# Schematic.net
KiCad netlist of a schematic drawn in Altium Designer
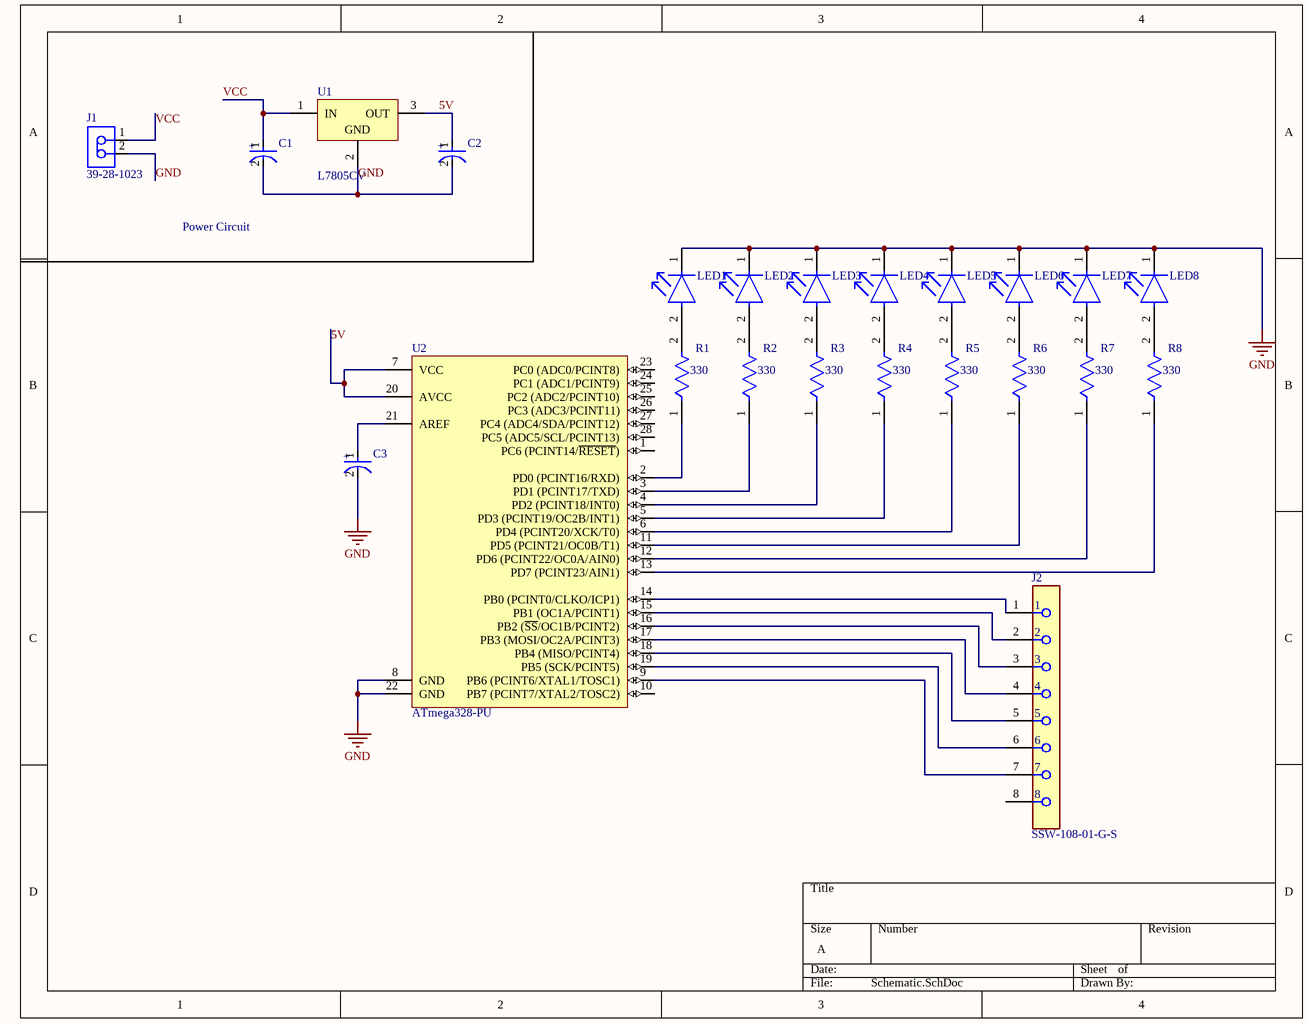
[diagram p0: Schematic.SchDoc]

(export (version "E")
  (design (tool "Eeschema 10.0.6"))
  (components
    (comp (ref "C1")
      (value "300nF")
      (footprint "FP-EEU-FC1V221L-MFG")
      (description "CAP ALUM 220UF 20% 35V RADIAL")
      (fields
        (field (name "OCTOPART") "https://octopart.com/eeu-fc1v221l-panasonic-39478519")
        (field (name "MANUFACTURER") "Panasonic Electronic Components")
      )
      (libsource (lib "Altium Content Vault") (part "385ce6c70a3ab0aa1e866f00bd8ed49"))
    )
    (comp (ref "C2")
      (value "100nF")
      (footprint "FP-EEU-FC1V221L-MFG")
      (description "CAP ALUM 220UF 20% 35V RADIAL")
      (fields
        (field (name "OCTOPART") "https://octopart.com/eeu-fc1v221l-panasonic-39478519")
        (field (name "MANUFACTURER") "Panasonic Electronic Components")
      )
      (libsource (lib "Altium Content Vault") (part "385ce6c70a3ab0aa1e866f00bd8ed49"))
    )
    (comp (ref "C3")
      (value "100nF")
      (footprint "FP-EEU-FC1V221L-MFG")
      (description "CAP ALUM 220UF 20% 35V RADIAL")
      (fields
        (field (name "OCTOPART") "https://octopart.com/eeu-fc1v221l-panasonic-39478519")
        (field (name "MANUFACTURER") "Panasonic Electronic Components")
      )
      (libsource (lib "Altium Content Vault") (part "385ce6c70a3ab0aa1e866f00bd8ed49"))
    )
    (comp (ref "J1")
      (value "39-28-1023")
      (footprint "MOLX-39-28-1023-2_V")
      (fields (field (name "MANUFACTURER") "Molex"))
      (libsource (lib "Altium Content Vault") (part "CN-2P-F-QF2"))
    )
    (comp (ref "J2")
      (value "SSW-108-01-G-S")
      (footprint "FP-SSW-108-01-G-S-MFG")
      (description "CONN RCPT 8POS 0.1 GOLD PCB")
      (libsource (lib "Altium Content Vault") (part "a32a9c29f5c2290c50060dfb8ad7212"))
    )
    (comp (ref "LED1")
      (value "HLMP-1719")
      (footprint "FP-HLMP-1719-MFG")
      (description "LED YELLOW DIFFUSED T-1 T/H")
      (fields
        (field (name "MANUFACTURER") "Broadcom")
        (field (name "OCTOPART") "https://octopart.com/hlmp-1719-broadcom-71130405")
      )
      (libsource (lib "Altium Content Vault") (part "8706943c75ba83719d021d2fdc84c58"))
    )
    (comp (ref "LED2")
      (value "HLMP-1719")
      (footprint "FP-HLMP-1719-MFG")
      (description "LED YELLOW DIFFUSED T-1 T/H")
      (fields
        (field (name "MANUFACTURER") "Broadcom")
        (field (name "OCTOPART") "https://octopart.com/hlmp-1719-broadcom-71130405")
      )
      (libsource (lib "Altium Content Vault") (part "8706943c75ba83719d021d2fdc84c58"))
    )
    (comp (ref "LED3")
      (value "HLMP-1719")
      (footprint "FP-HLMP-1719-MFG")
      (description "LED YELLOW DIFFUSED T-1 T/H")
      (fields
        (field (name "MANUFACTURER") "Broadcom")
        (field (name "OCTOPART") "https://octopart.com/hlmp-1719-broadcom-71130405")
      )
      (libsource (lib "Altium Content Vault") (part "8706943c75ba83719d021d2fdc84c58"))
    )
    (comp (ref "LED4")
      (value "HLMP-1719")
      (footprint "FP-HLMP-1719-MFG")
      (description "LED YELLOW DIFFUSED T-1 T/H")
      (fields
        (field (name "MANUFACTURER") "Broadcom")
        (field (name "OCTOPART") "https://octopart.com/hlmp-1719-broadcom-71130405")
      )
      (libsource (lib "Altium Content Vault") (part "8706943c75ba83719d021d2fdc84c58"))
    )
    (comp (ref "LED5")
      (value "HLMP-1719")
      (footprint "FP-HLMP-1719-MFG")
      (description "LED YELLOW DIFFUSED T-1 T/H")
      (fields
        (field (name "MANUFACTURER") "Broadcom")
        (field (name "OCTOPART") "https://octopart.com/hlmp-1719-broadcom-71130405")
      )
      (libsource (lib "Altium Content Vault") (part "8706943c75ba83719d021d2fdc84c58"))
    )
    (comp (ref "LED6")
      (value "HLMP-1719")
      (footprint "FP-HLMP-1719-MFG")
      (description "LED YELLOW DIFFUSED T-1 T/H")
      (fields
        (field (name "MANUFACTURER") "Broadcom")
        (field (name "OCTOPART") "https://octopart.com/hlmp-1719-broadcom-71130405")
      )
      (libsource (lib "Altium Content Vault") (part "8706943c75ba83719d021d2fdc84c58"))
    )
    (comp (ref "LED7")
      (value "HLMP-1719")
      (footprint "FP-HLMP-1719-MFG")
      (description "LED YELLOW DIFFUSED T-1 T/H")
      (fields
        (field (name "MANUFACTURER") "Broadcom")
        (field (name "OCTOPART") "https://octopart.com/hlmp-1719-broadcom-71130405")
      )
      (libsource (lib "Altium Content Vault") (part "8706943c75ba83719d021d2fdc84c58"))
    )
    (comp (ref "LED8")
      (value "HLMP-1719")
      (footprint "FP-HLMP-1719-MFG")
      (description "LED YELLOW DIFFUSED T-1 T/H")
      (fields
        (field (name "MANUFACTURER") "Broadcom")
        (field (name "OCTOPART") "https://octopart.com/hlmp-1719-broadcom-71130405")
      )
      (libsource (lib "Altium Content Vault") (part "8706943c75ba83719d021d2fdc84c58"))
    )
    (comp (ref "R1")
      (value "330")
      (footprint "FP-MFR-25-MFG")
      (description "RES 1.18K OHM 1/4W 1% AXIAL")
      (fields (field (name "MANUFACTURER") "Yageo") (field (name "TOLERANCE") "1%"))
      (libsource (lib "Altium Content Vault") (part "1029c3af85768c4190bb7ad29bc67b5"))
    )
    (comp (ref "R2")
      (value "330")
      (footprint "FP-MFR-25-MFG")
      (description "RES 1.18K OHM 1/4W 1% AXIAL")
      (fields (field (name "MANUFACTURER") "Yageo") (field (name "TOLERANCE") "1%"))
      (libsource (lib "Altium Content Vault") (part "1029c3af85768c4190bb7ad29bc67b5"))
    )
    (comp (ref "R3")
      (value "330")
      (footprint "FP-MFR-25-MFG")
      (description "RES 1.18K OHM 1/4W 1% AXIAL")
      (fields (field (name "MANUFACTURER") "Yageo") (field (name "TOLERANCE") "1%"))
      (libsource (lib "Altium Content Vault") (part "1029c3af85768c4190bb7ad29bc67b5"))
    )
    (comp (ref "R4")
      (value "330")
      (footprint "FP-MFR-25-MFG")
      (description "RES 1.18K OHM 1/4W 1% AXIAL")
      (fields (field (name "MANUFACTURER") "Yageo") (field (name "TOLERANCE") "1%"))
      (libsource (lib "Altium Content Vault") (part "1029c3af85768c4190bb7ad29bc67b5"))
    )
    (comp (ref "R5")
      (value "330")
      (footprint "FP-MFR-25-MFG")
      (description "RES 1.18K OHM 1/4W 1% AXIAL")
      (fields (field (name "MANUFACTURER") "Yageo") (field (name "TOLERANCE") "1%"))
      (libsource (lib "Altium Content Vault") (part "1029c3af85768c4190bb7ad29bc67b5"))
    )
    (comp (ref "R6")
      (value "330")
      (footprint "FP-MFR-25-MFG")
      (description "RES 1.18K OHM 1/4W 1% AXIAL")
      (fields (field (name "MANUFACTURER") "Yageo") (field (name "TOLERANCE") "1%"))
      (libsource (lib "Altium Content Vault") (part "1029c3af85768c4190bb7ad29bc67b5"))
    )
    (comp (ref "R7")
      (value "330")
      (footprint "FP-MFR-25-MFG")
      (description "RES 1.18K OHM 1/4W 1% AXIAL")
      (fields (field (name "MANUFACTURER") "Yageo") (field (name "TOLERANCE") "1%"))
      (libsource (lib "Altium Content Vault") (part "1029c3af85768c4190bb7ad29bc67b5"))
    )
    (comp (ref "R8")
      (value "330")
      (footprint "FP-MFR-25-MFG")
      (description "RES 1.18K OHM 1/4W 1% AXIAL")
      (fields (field (name "MANUFACTURER") "Yageo") (field (name "TOLERANCE") "1%"))
      (libsource (lib "Altium Content Vault") (part "1029c3af85768c4190bb7ad29bc67b5"))
    )
    (comp (ref "U1")
      (value "L7805CV")
      (footprint "TO220")
      (description "Positive Voltage Regulator, 5V, 3-Pin TO-220")
      (libsource (lib "Altium Content Vault") (part "PM-REG-L4940-SIL3"))
    )
    (comp (ref "U2")
      (value "ATmega328-PU")
      (footprint "28P3")
      (libsource (lib "Altium Content Vault") (part "MC-8B-ATM48-IL28"))
    )
  )
  (nets
    (net (code "1") (name "/5V") (class "Default")
      (node (ref "C2") (pin "1") (pinfunction "C_1") (pintype "passive"))
      (node (ref "U1") (pin "3") (pinfunction "OUT_3") (pintype "power_in"))
      (node (ref "U2") (pin "20") (pinfunction "AVCC_20") (pintype "power_in"))
      (node (ref "U2") (pin "7") (pinfunction "VCC_7") (pintype "power_in"))
    )
    (net (code "2") (name "/VCC") (class "Default")
      (node (ref "C1") (pin "1") (pinfunction "C_1") (pintype "passive"))
      (node (ref "J1") (pin "1") (pinfunction "1_1") (pintype "passive"))
      (node (ref "U1") (pin "1") (pinfunction "IN_1") (pintype "power_in"))
    )
    (net (code "3") (name "GND") (class "Default")
      (node (ref "C1") (pin "2") (pinfunction "A_2") (pintype "passive"))
      (node (ref "C2") (pin "2") (pinfunction "A_2") (pintype "passive"))
      (node (ref "C3") (pin "2") (pinfunction "A_2") (pintype "passive"))
      (node (ref "J1") (pin "2") (pinfunction "2_2") (pintype "passive"))
      (node (ref "LED1") (pin "1") (pinfunction "C_1") (pintype "passive"))
      (node (ref "LED2") (pin "1") (pinfunction "C_1") (pintype "passive"))
      (node (ref "LED3") (pin "1") (pinfunction "C_1") (pintype "passive"))
      (node (ref "LED4") (pin "1") (pinfunction "C_1") (pintype "passive"))
      (node (ref "LED5") (pin "1") (pinfunction "C_1") (pintype "passive"))
      (node (ref "LED6") (pin "1") (pinfunction "C_1") (pintype "passive"))
      (node (ref "LED7") (pin "1") (pinfunction "C_1") (pintype "passive"))
      (node (ref "LED8") (pin "1") (pinfunction "C_1") (pintype "passive"))
      (node (ref "U1") (pin "2") (pinfunction "GND_2") (pintype "power_in"))
      (node (ref "U2") (pin "22") (pinfunction "GND_22") (pintype "power_in"))
      (node (ref "U2") (pin "8") (pinfunction "GND_8") (pintype "power_in"))
    )
    (net (code "4") (name "Net-(C3-C)") (class "Default")
      (node (ref "C3") (pin "1") (pinfunction "C_1") (pintype "passive"))
      (node (ref "U2") (pin "21") (pinfunction "AREF_21") (pintype "power_in"))
    )
    (net (code "5") (name "Net-(LED1-A)") (class "Default")
      (node (ref "LED1") (pin "2") (pinfunction "A_2") (pintype "passive"))
      (node (ref "R1") (pin "2") (pinfunction "2_2") (pintype "passive"))
    )
    (net (code "6") (name "Net-(LED2-A)") (class "Default")
      (node (ref "LED2") (pin "2") (pinfunction "A_2") (pintype "passive"))
      (node (ref "R2") (pin "2") (pinfunction "2_2") (pintype "passive"))
    )
    (net (code "7") (name "Net-(LED3-A)") (class "Default")
      (node (ref "LED3") (pin "2") (pinfunction "A_2") (pintype "passive"))
      (node (ref "R3") (pin "2") (pinfunction "2_2") (pintype "passive"))
    )
    (net (code "8") (name "Net-(LED4-A)") (class "Default")
      (node (ref "LED4") (pin "2") (pinfunction "A_2") (pintype "passive"))
      (node (ref "R4") (pin "2") (pinfunction "2_2") (pintype "passive"))
    )
    (net (code "9") (name "Net-(LED5-A)") (class "Default")
      (node (ref "LED5") (pin "2") (pinfunction "A_2") (pintype "passive"))
      (node (ref "R5") (pin "2") (pinfunction "2_2") (pintype "passive"))
    )
    (net (code "10") (name "Net-(LED6-A)") (class "Default")
      (node (ref "LED6") (pin "2") (pinfunction "A_2") (pintype "passive"))
      (node (ref "R6") (pin "2") (pinfunction "2_2") (pintype "passive"))
    )
    (net (code "11") (name "Net-(LED7-A)") (class "Default")
      (node (ref "LED7") (pin "2") (pinfunction "A_2") (pintype "passive"))
      (node (ref "R7") (pin "2") (pinfunction "2_2") (pintype "passive"))
    )
    (net (code "12") (name "Net-(LED8-A)") (class "Default")
      (node (ref "LED8") (pin "2") (pinfunction "A_2") (pintype "passive"))
      (node (ref "R8") (pin "2") (pinfunction "2_2") (pintype "passive"))
    )
    (net (code "13") (name "Net-(U2-PB0_(PCINT0{slash}CLKO{slash}ICP1))") (class "Default")
      (node (ref "J2") (pin "1") (pinfunction "1_1") (pintype "passive"))
      (node (ref "U2") (pin "14") (pinfunction "PB0_(PCINT0/CLKO/ICP1)_14") (pintype "bidirectional"))
    )
    (net (code "14") (name "Net-(U2-PB1_(OC1A{slash}PCINT1))") (class "Default")
      (node (ref "J2") (pin "2") (pinfunction "2_2") (pintype "passive"))
      (node (ref "U2") (pin "15") (pinfunction "PB1_(OC1A/PCINT1)_15") (pintype "bidirectional"))
    )
    (net (code "15") (name "Net-(U2-PB2_(~{SS}{slash}OC1B{slash}PCINT2))") (class "Default")
      (node (ref "J2") (pin "3") (pinfunction "3_3") (pintype "passive"))
      (node (ref "U2") (pin "16") (pinfunction "PB2_(~{SS}/OC1B/PCINT2)_16") (pintype "bidirectional"))
    )
    (net (code "16") (name "Net-(U2-PB3_(MOSI{slash}OC2A{slash}PCINT3))") (class "Default")
      (node (ref "J2") (pin "4") (pinfunction "4_4") (pintype "passive"))
      (node (ref "U2") (pin "17") (pinfunction "PB3_(MOSI/OC2A/PCINT3)_17") (pintype "bidirectional"))
    )
    (net (code "17") (name "Net-(U2-PB4_(MISO{slash}PCINT4))") (class "Default")
      (node (ref "J2") (pin "5") (pinfunction "5_5") (pintype "passive"))
      (node (ref "U2") (pin "18") (pinfunction "PB4_(MISO/PCINT4)_18") (pintype "bidirectional"))
    )
    (net (code "18") (name "Net-(U2-PB5_(SCK{slash}PCINT5))") (class "Default")
      (node (ref "J2") (pin "6") (pinfunction "6_6") (pintype "passive"))
      (node (ref "U2") (pin "19") (pinfunction "PB5_(SCK/PCINT5)_19") (pintype "bidirectional"))
    )
    (net (code "19") (name "Net-(U2-PB6_(PCINT6{slash}XTAL1{slash}TOSC1))") (class "Default")
      (node (ref "J2") (pin "7") (pinfunction "7_7") (pintype "passive"))
      (node (ref "U2") (pin "9") (pinfunction "PB6_(PCINT6/XTAL1/TOSC1)_9") (pintype "bidirectional"))
    )
    (net (code "20") (name "Net-(U2-PD0_(PCINT16{slash}RXD))") (class "Default")
      (node (ref "R1") (pin "1") (pinfunction "1_1") (pintype "passive"))
      (node (ref "U2") (pin "2") (pinfunction "PD0_(PCINT16/RXD)_2") (pintype "bidirectional"))
    )
    (net (code "21") (name "Net-(U2-PD1_(PCINT17{slash}TXD))") (class "Default")
      (node (ref "R2") (pin "1") (pinfunction "1_1") (pintype "passive"))
      (node (ref "U2") (pin "3") (pinfunction "PD1_(PCINT17/TXD)_3") (pintype "bidirectional"))
    )
    (net (code "22") (name "Net-(U2-PD2_(PCINT18{slash}INT0))") (class "Default")
      (node (ref "R3") (pin "1") (pinfunction "1_1") (pintype "passive"))
      (node (ref "U2") (pin "4") (pinfunction "PD2_(PCINT18/INT0)_4") (pintype "bidirectional"))
    )
    (net (code "23") (name "Net-(U2-PD3_(PCINT19{slash}OC2B{slash}INT1))") (class "Default")
      (node (ref "R4") (pin "1") (pinfunction "1_1") (pintype "passive"))
      (node (ref "U2") (pin "5") (pinfunction "PD3_(PCINT19/OC2B/INT1)_5") (pintype "bidirectional"))
    )
    (net (code "24") (name "Net-(U2-PD4_(PCINT20{slash}XCK{slash}T0))") (class "Default")
      (node (ref "R5") (pin "1") (pinfunction "1_1") (pintype "passive"))
      (node (ref "U2") (pin "6") (pinfunction "PD4_(PCINT20/XCK/T0)_6") (pintype "bidirectional"))
    )
    (net (code "25") (name "Net-(U2-PD5_(PCINT21{slash}OC0B{slash}T1))") (class "Default")
      (node (ref "R6") (pin "1") (pinfunction "1_1") (pintype "passive"))
      (node (ref "U2") (pin "11") (pinfunction "PD5_(PCINT21/OC0B/T1)_11") (pintype "bidirectional"))
    )
    (net (code "26") (name "Net-(U2-PD6_(PCINT22{slash}OC0A{slash}AIN0))") (class "Default")
      (node (ref "R7") (pin "1") (pinfunction "1_1") (pintype "passive"))
      (node (ref "U2") (pin "12") (pinfunction "PD6_(PCINT22/OC0A/AIN0)_12") (pintype "bidirectional"))
    )
    (net (code "27") (name "Net-(U2-PD7_(PCINT23{slash}AIN1))") (class "Default")
      (node (ref "R8") (pin "1") (pinfunction "1_1") (pintype "passive"))
      (node (ref "U2") (pin "13") (pinfunction "PD7_(PCINT23/AIN1)_13") (pintype "bidirectional"))
    )
    (net (code "28") (name "unconnected-(J2-Pad8)") (class "Default")
      (node (ref "J2") (pin "8") (pinfunction "8_8") (pintype "passive"))
    )
    (net (code "29") (name "unconnected-(U2-PB7_(PCINT7{slash}XTAL2{slash}TOSC2)-Pad10)") (class "Default")
      (node (ref "U2") (pin "10") (pinfunction "PB7_(PCINT7/XTAL2/TOSC2)_10") (pintype "bidirectional"))
    )
    (net (code "30") (name "unconnected-(U2-PC0_(ADC0{slash}PCINT8)-Pad23)") (class "Default")
      (node (ref "U2") (pin "23") (pinfunction "PC0_(ADC0/PCINT8)_23") (pintype "bidirectional"))
    )
    (net (code "31") (name "unconnected-(U2-PC1_(ADC1{slash}PCINT9)-Pad24)") (class "Default")
      (node (ref "U2") (pin "24") (pinfunction "PC1_(ADC1/PCINT9)_24") (pintype "bidirectional"))
    )
    (net (code "32") (name "unconnected-(U2-PC2_(ADC2{slash}PCINT10)-Pad25)") (class "Default")
      (node (ref "U2") (pin "25") (pinfunction "PC2_(ADC2/PCINT10)_25") (pintype "bidirectional"))
    )
    (net (code "33") (name "unconnected-(U2-PC3_(ADC3{slash}PCINT11)-Pad26)") (class "Default")
      (node (ref "U2") (pin "26") (pinfunction "PC3_(ADC3/PCINT11)_26") (pintype "bidirectional"))
    )
    (net (code "34") (name "unconnected-(U2-PC4_(ADC4{slash}SDA{slash}PCINT12)-Pad27)") (class "Default")
      (node (ref "U2") (pin "27") (pinfunction "PC4_(ADC4/SDA/PCINT12)_27") (pintype "bidirectional"))
    )
    (net (code "35") (name "unconnected-(U2-PC5_(ADC5{slash}SCL{slash}PCINT13)-Pad28)") (class "Default")
      (node (ref "U2") (pin "28") (pinfunction "PC5_(ADC5/SCL/PCINT13)_28") (pintype "bidirectional"))
    )
    (net (code "36") (name "unconnected-(U2-PC6_(PCINT14{slash}~{RESET})-Pad1)") (class "Default")
      (node (ref "U2") (pin "1") (pinfunction "PC6_(PCINT14/~{RESET})_1") (pintype "bidirectional"))
    )
  )
)
